# power_hub.net
KiCad netlist of a schematic drawn in EAGLE
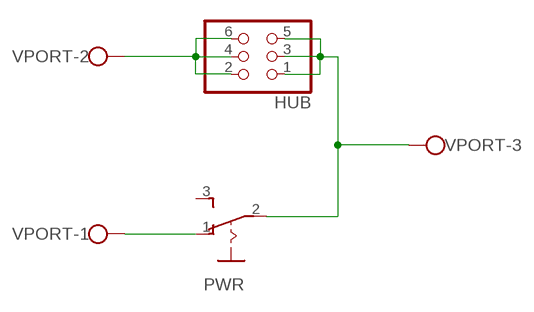
[diagram p0: schematic, sheet 1]

(export (version "E")
  (design (tool "Eeschema 10.0.6"))
  (components
    (comp (ref "HUB")
      (value "PINHD-2X3")
      (footprint "eagle-import:2X03")
      (libsource (lib "eagle-import") (part "PINHD-2X3"))
    )
    (comp (ref "PWR")
      (value "M251")
      (footprint "eagle-import:M251")
      (libsource (lib "eagle-import") (part "M251"))
    )
    (comp (ref "VPORT")
      (value "W237-103")
      (footprint "eagle-import:W237-103")
      (fields (field (name "MPN") "237-103"))
      (libsource (lib "eagle-import") (part "W237-103"))
    )
  )
  (nets
    (net (code "1") (name "Net-(PWR-O)") (class "Default")
      (node (ref "PWR") (pin "1") (pinfunction "O_1") (pintype "passive"))
      (node (ref "VPORT") (pin "1") (pinfunction "KL_1") (pintype "passive"))
    )
    (net (code "2") (name "Net-(PWR-P)") (class "Default")
      (node (ref "HUB") (pin "1") (pinfunction "1_1") (pintype "passive"))
      (node (ref "HUB") (pin "3") (pinfunction "3_3") (pintype "passive"))
      (node (ref "HUB") (pin "5") (pinfunction "5_5") (pintype "passive"))
      (node (ref "PWR") (pin "2") (pinfunction "P_2") (pintype "passive"))
      (node (ref "VPORT") (pin "3") (pinfunction "KL_3") (pintype "passive"))
    )
    (net (code "3") (name "Net-(VPORTB-KL)") (class "Default")
      (node (ref "HUB") (pin "2") (pinfunction "2_2") (pintype "passive"))
      (node (ref "HUB") (pin "4") (pinfunction "4_4") (pintype "passive"))
      (node (ref "HUB") (pin "6") (pinfunction "6_6") (pintype "passive"))
      (node (ref "VPORT") (pin "2") (pinfunction "KL_2") (pintype "passive"))
    )
    (net (code "4") (name "unconnected-(PWR-S-Pad3)") (class "Default")
      (node (ref "PWR") (pin "3") (pinfunction "S_3") (pintype "passive"))
    )
  )
)
